# LTC6820_chip.net
KiCad netlist of a schematic drawn in Altium Designer
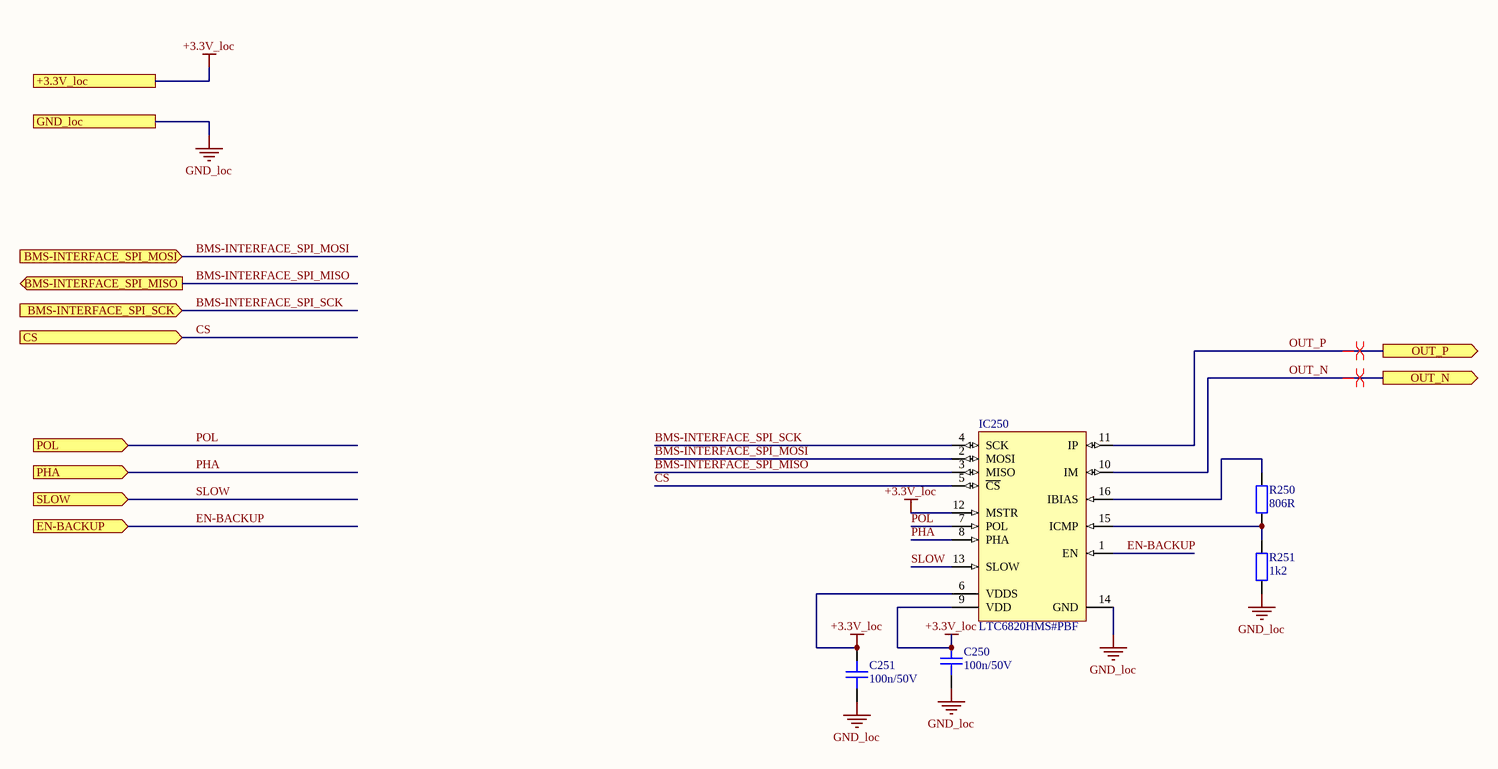
[diagram p0: LTC6820_chip.SchDoc]

(export (version "E")
  (design (tool "Eeschema 10.0.6"))
  (components
    (comp (ref "C250")
      (value "100n/50V")
      (footprint "CAPC1608X08N")
      (description "MLCC")
      (fields (field (name "PART NUMBER") "gen_C_ceramic_100n_50V_X7R_0603"))
      (libsource (lib "OE750") (part "C"))
    )
    (comp (ref "C251")
      (value "100n/50V")
      (footprint "CAPC1608X08N")
      (description "MLCC")
      (fields (field (name "PART NUMBER") "gen_C_ceramic_100n_50V_X7R_0603"))
      (libsource (lib "OE750") (part "C"))
    )
    (comp (ref "IC250")
      (value "LTC6820HMS#PBF")
      (footprint "LT-MS-16_M")
      (description "IsoSPI Isolated Communication Interface, 2.7 to 5.5 V, -40 to 125 degC, 16-Pin MSOP (MS), Pb-Free")
      (fields (field (name "MANUFACTURER") "Linear Technology"))
      (libsource (lib "Altium Content Vault") (part "LT-LTC6820-MS-16"))
    )
    (comp (ref "R250")
      (value "806R")
      (footprint "RESC1608X05N")
      (description "SMD Resistor 806R 0603")
      (fields (field (name "PART NUMBER") "gen_R_806R_0603") (field (name "TOLERANCE") "1%"))
      (libsource (lib "OE750") (part "R"))
    )
    (comp (ref "R251")
      (value "1k2")
      (footprint "RESC1608X05N")
      (description "SMD Resistor 1k2 0603")
      (fields (field (name "PART NUMBER") "gen_R_1k2_0603") (field (name "TOLERANCE") "1%"))
      (libsource (lib "OE750") (part "R"))
    )
  )
  (nets
    (net (code "1") (name "+3.3V_loc") (class "Default")
      (node (ref "C250") (pin "2") (pinfunction "2_2") (pintype "passive"))
      (node (ref "C251") (pin "2") (pinfunction "2_2") (pintype "passive"))
      (node (ref "IC250") (pin "12") (pinfunction "MSTR_12") (pintype "input"))
      (node (ref "IC250") (pin "6") (pinfunction "VDDS_6") (pintype "power_in"))
      (node (ref "IC250") (pin "9") (pinfunction "VDD_9") (pintype "power_in"))
    )
    (net (code "2") (name "/BMS-INTERFACE_SPI_MISO") (class "Default")
      (node (ref "IC250") (pin "3") (pinfunction "MISO_3") (pintype "bidirectional"))
    )
    (net (code "3") (name "/BMS-INTERFACE_SPI_MOSI") (class "Default")
      (node (ref "IC250") (pin "2") (pinfunction "MOSI_2") (pintype "bidirectional"))
    )
    (net (code "4") (name "/BMS-INTERFACE_SPI_SCK") (class "Default")
      (node (ref "IC250") (pin "4") (pinfunction "SCK_4") (pintype "bidirectional"))
    )
    (net (code "5") (name "/CS") (class "Default")
      (node (ref "IC250") (pin "5") (pinfunction "~{CS}_5") (pintype "bidirectional"))
    )
    (net (code "6") (name "/EN-BACKUP") (class "Default")
      (node (ref "IC250") (pin "1") (pinfunction "EN_1") (pintype "input"))
    )
    (net (code "7") (name "/OUT_N") (class "Default")
      (node (ref "IC250") (pin "10") (pinfunction "IM_10") (pintype "bidirectional"))
    )
    (net (code "8") (name "/OUT_P") (class "Default")
      (node (ref "IC250") (pin "11") (pinfunction "IP_11") (pintype "bidirectional"))
    )
    (net (code "9") (name "/PHA") (class "Default")
      (node (ref "IC250") (pin "8") (pinfunction "PHA_8") (pintype "input"))
    )
    (net (code "10") (name "/POL") (class "Default")
      (node (ref "IC250") (pin "7") (pinfunction "POL_7") (pintype "input"))
    )
    (net (code "11") (name "/SLOW") (class "Default")
      (node (ref "IC250") (pin "13") (pinfunction "SLOW_13") (pintype "input"))
    )
    (net (code "12") (name "GND_loc") (class "Default")
      (node (ref "C250") (pin "1") (pinfunction "1_1") (pintype "passive"))
      (node (ref "C251") (pin "1") (pinfunction "1_1") (pintype "passive"))
      (node (ref "IC250") (pin "14") (pinfunction "GND_14") (pintype "power_in"))
      (node (ref "R251") (pin "1") (pinfunction "1_1") (pintype "passive"))
    )
    (net (code "13") (name "Net-(IC250-IBIAS)") (class "Default")
      (node (ref "IC250") (pin "16") (pinfunction "IBIAS_16") (pintype "input"))
      (node (ref "R250") (pin "2") (pinfunction "2_2") (pintype "passive"))
    )
    (net (code "14") (name "Net-(IC250-ICMP)") (class "Default")
      (node (ref "IC250") (pin "15") (pinfunction "ICMP_15") (pintype "input"))
      (node (ref "R250") (pin "1") (pinfunction "1_1") (pintype "passive"))
      (node (ref "R251") (pin "2") (pinfunction "2_2") (pintype "passive"))
    )
  )
)
